# Frame.net
KiCad netlist of a schematic drawn in Altium Designer
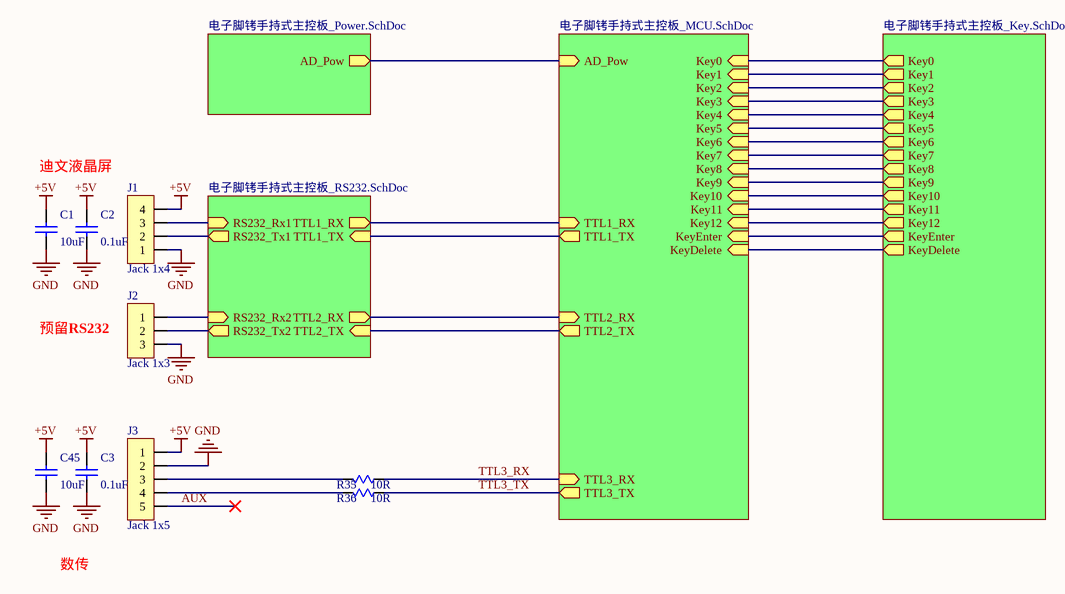
[diagram p0: 电子脚铐手持式主控板_Frame.SchDoc]

(export (version "E")
  (design (tool "Eeschema 10.0.6"))
  (components
    (comp (ref "C1")
      (value "10uF")
      (footprint "C0603")
      (description "CAP")
      (fields (field (name "PUBLISHER") "Altium Limited"))
      (libsource (lib "Passive Components Class") (part "CAP"))
    )
    (comp (ref "C2")
      (value "0.1uF")
      (footprint "C0603")
      (description "CAP")
      (fields (field (name "PUBLISHER") "Altium Limited"))
      (libsource (lib "Passive Components Class") (part "CAP"))
    )
    (comp (ref "C3")
      (value "0.1uF")
      (footprint "C0603")
      (description "CAP")
      (fields (field (name "PUBLISHER") "Altium Limited"))
      (libsource (lib "Passive Components Class") (part "CAP"))
    )
    (comp (ref "C45")
      (value "10uF")
      (footprint "C0603")
      (description "CAP")
      (fields (field (name "PUBLISHER") "Altium Limited"))
      (libsource (lib "Passive Components Class") (part "CAP"))
    )
    (comp (ref "J1")
      (value "Jack 1x4")
      (footprint "XH-4AW")
      (description "插座")
      (libsource (lib "Connector") (part "Jack 1x4"))
    )
    (comp (ref "J2")
      (value "Jack 1x3")
      (footprint "XH-3AW")
      (description "插座")
      (libsource (lib "Connector") (part "Jack 1x3"))
    )
    (comp (ref "J3")
      (value "Jack 1x5")
      (footprint "PH-5A")
      (description "插座")
      (libsource (lib "Connector") (part "Jack 1x5"))
    )
    (comp (ref "R35")
      (value "10R")
      (footprint "R0603")
      (description "Resistor")
      (fields (field (name "PUBLISHER") "Altium Limited"))
      (libsource (lib "Temp") (part "Res"))
    )
    (comp (ref "R36")
      (value "10R")
      (footprint "R0603")
      (description "Resistor")
      (fields (field (name "PUBLISHER") "Altium Limited"))
      (libsource (lib "Temp") (part "Res"))
    )
  )
  (nets
    (net (code "1") (name "+5V") (class "Default")
      (node (ref "C1") (pin "1") (pinfunction "1_1") (pintype "passive"))
      (node (ref "C2") (pin "1") (pinfunction "1_1") (pintype "passive"))
      (node (ref "C3") (pin "1") (pinfunction "1_1") (pintype "passive"))
      (node (ref "C45") (pin "1") (pinfunction "1_1") (pintype "passive"))
      (node (ref "J1") (pin "4") (pinfunction "4_4") (pintype "passive"))
      (node (ref "J3") (pin "1") (pinfunction "1_1") (pintype "passive"))
    )
    (net (code "3") (name "/AUX") (class "Default")
      (node (ref "J3") (pin "5") (pinfunction "5_5") (pintype "passive+no_connect"))
    )
    (net (code "19") (name "/RS232_Rx1") (class "Default")
      (node (ref "J1") (pin "3") (pinfunction "3_3") (pintype "passive"))
    )
    (net (code "20") (name "/RS232_Rx2") (class "Default")
      (node (ref "J2") (pin "1") (pinfunction "1_1") (pintype "passive"))
    )
    (net (code "21") (name "/RS232_Tx1") (class "Default")
      (node (ref "J1") (pin "2") (pinfunction "2_2") (pintype "passive"))
    )
    (net (code "22") (name "/RS232_Tx2") (class "Default")
      (node (ref "J2") (pin "2") (pinfunction "2_2") (pintype "passive"))
    )
    (net (code "27") (name "/TTL3_RX") (class "Default")
      (node (ref "R35") (pin "2") (pinfunction "2_2") (pintype "passive"))
    )
    (net (code "28") (name "/TTL3_TX") (class "Default")
      (node (ref "R36") (pin "2") (pinfunction "2_2") (pintype "passive"))
    )
    (net (code "29") (name "GND") (class "Default")
      (node (ref "C1") (pin "2") (pinfunction "2_2") (pintype "passive"))
      (node (ref "C2") (pin "2") (pinfunction "2_2") (pintype "passive"))
      (node (ref "C3") (pin "2") (pinfunction "2_2") (pintype "passive"))
      (node (ref "C45") (pin "2") (pinfunction "2_2") (pintype "passive"))
      (node (ref "J1") (pin "1") (pinfunction "1_1") (pintype "passive"))
      (node (ref "J2") (pin "3") (pinfunction "3_3") (pintype "passive"))
      (node (ref "J3") (pin "2") (pinfunction "2_2") (pintype "passive"))
    )
    (net (code "30") (name "Net-(J3-Pad3)") (class "Default")
      (node (ref "J3") (pin "3") (pinfunction "3_3") (pintype "passive"))
      (node (ref "R35") (pin "1") (pinfunction "1_1") (pintype "passive"))
    )
    (net (code "31") (name "Net-(J3-Pad4)") (class "Default")
      (node (ref "J3") (pin "4") (pinfunction "4_4") (pintype "passive"))
      (node (ref "R36") (pin "1") (pinfunction "1_1") (pintype "passive"))
    )
  )
)
